# S7CAS-PLEIADES-CARTE-MERE_P06_POWER2.net
KiCad netlist of a schematic drawn in Altium Designer
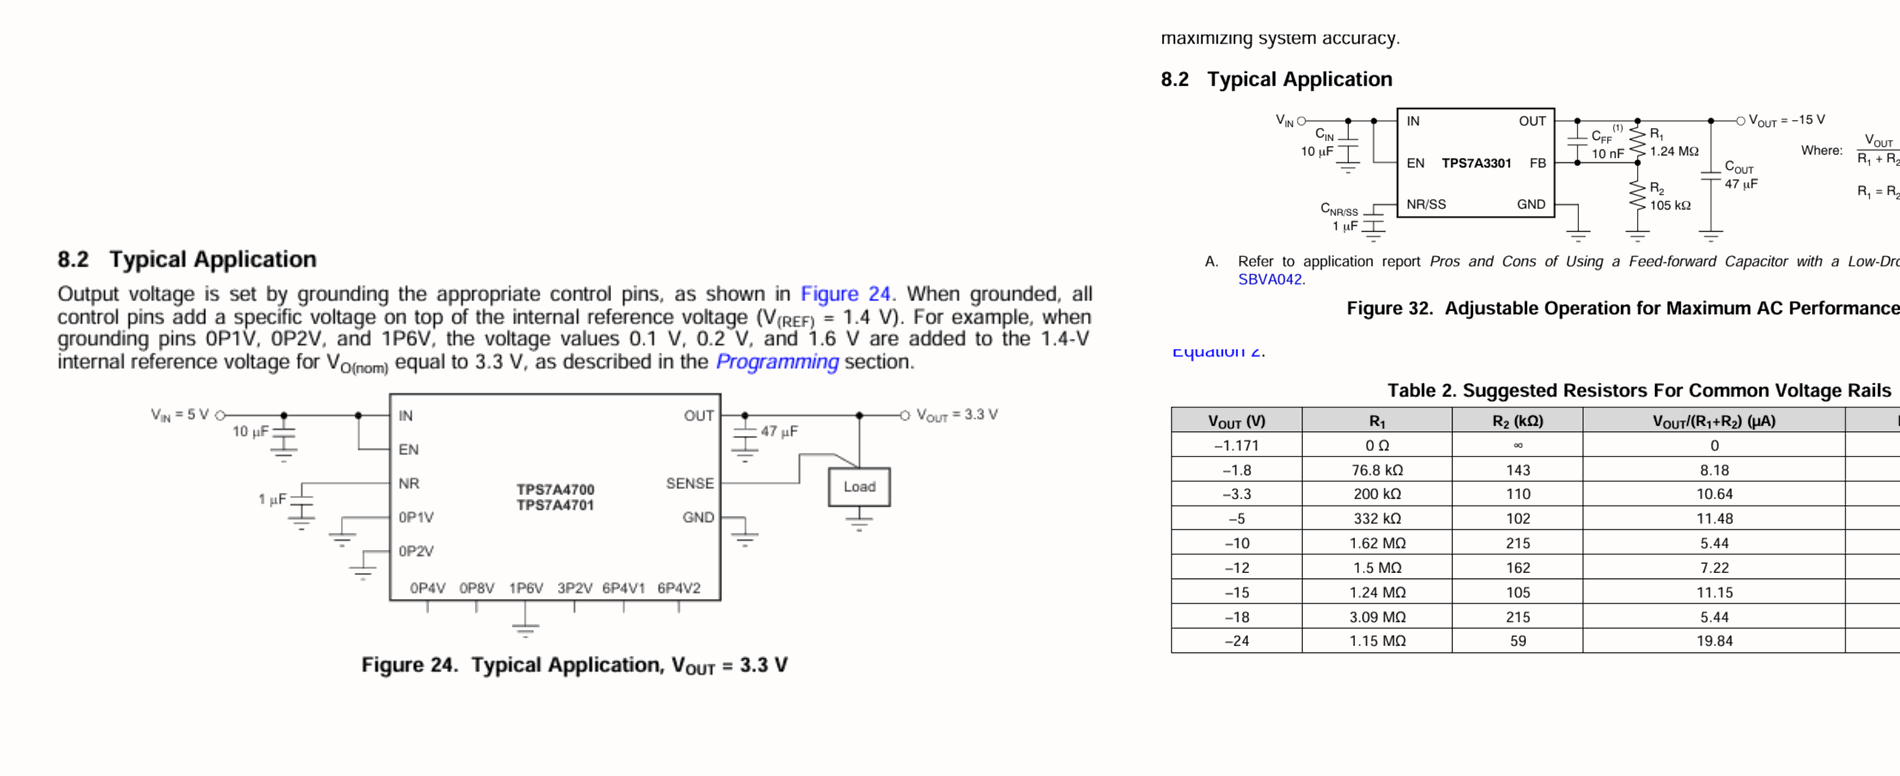
[diagram p0: S7CAS-PLEIADES-CARTE-MERE_P06_POWER2.SCHDOC, top left]
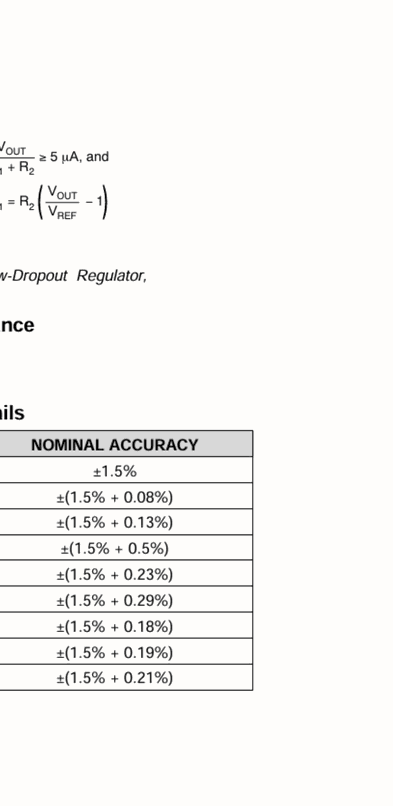
[diagram p1: S7CAS-PLEIADES-CARTE-MERE_P06_POWER2.SCHDOC, top right]
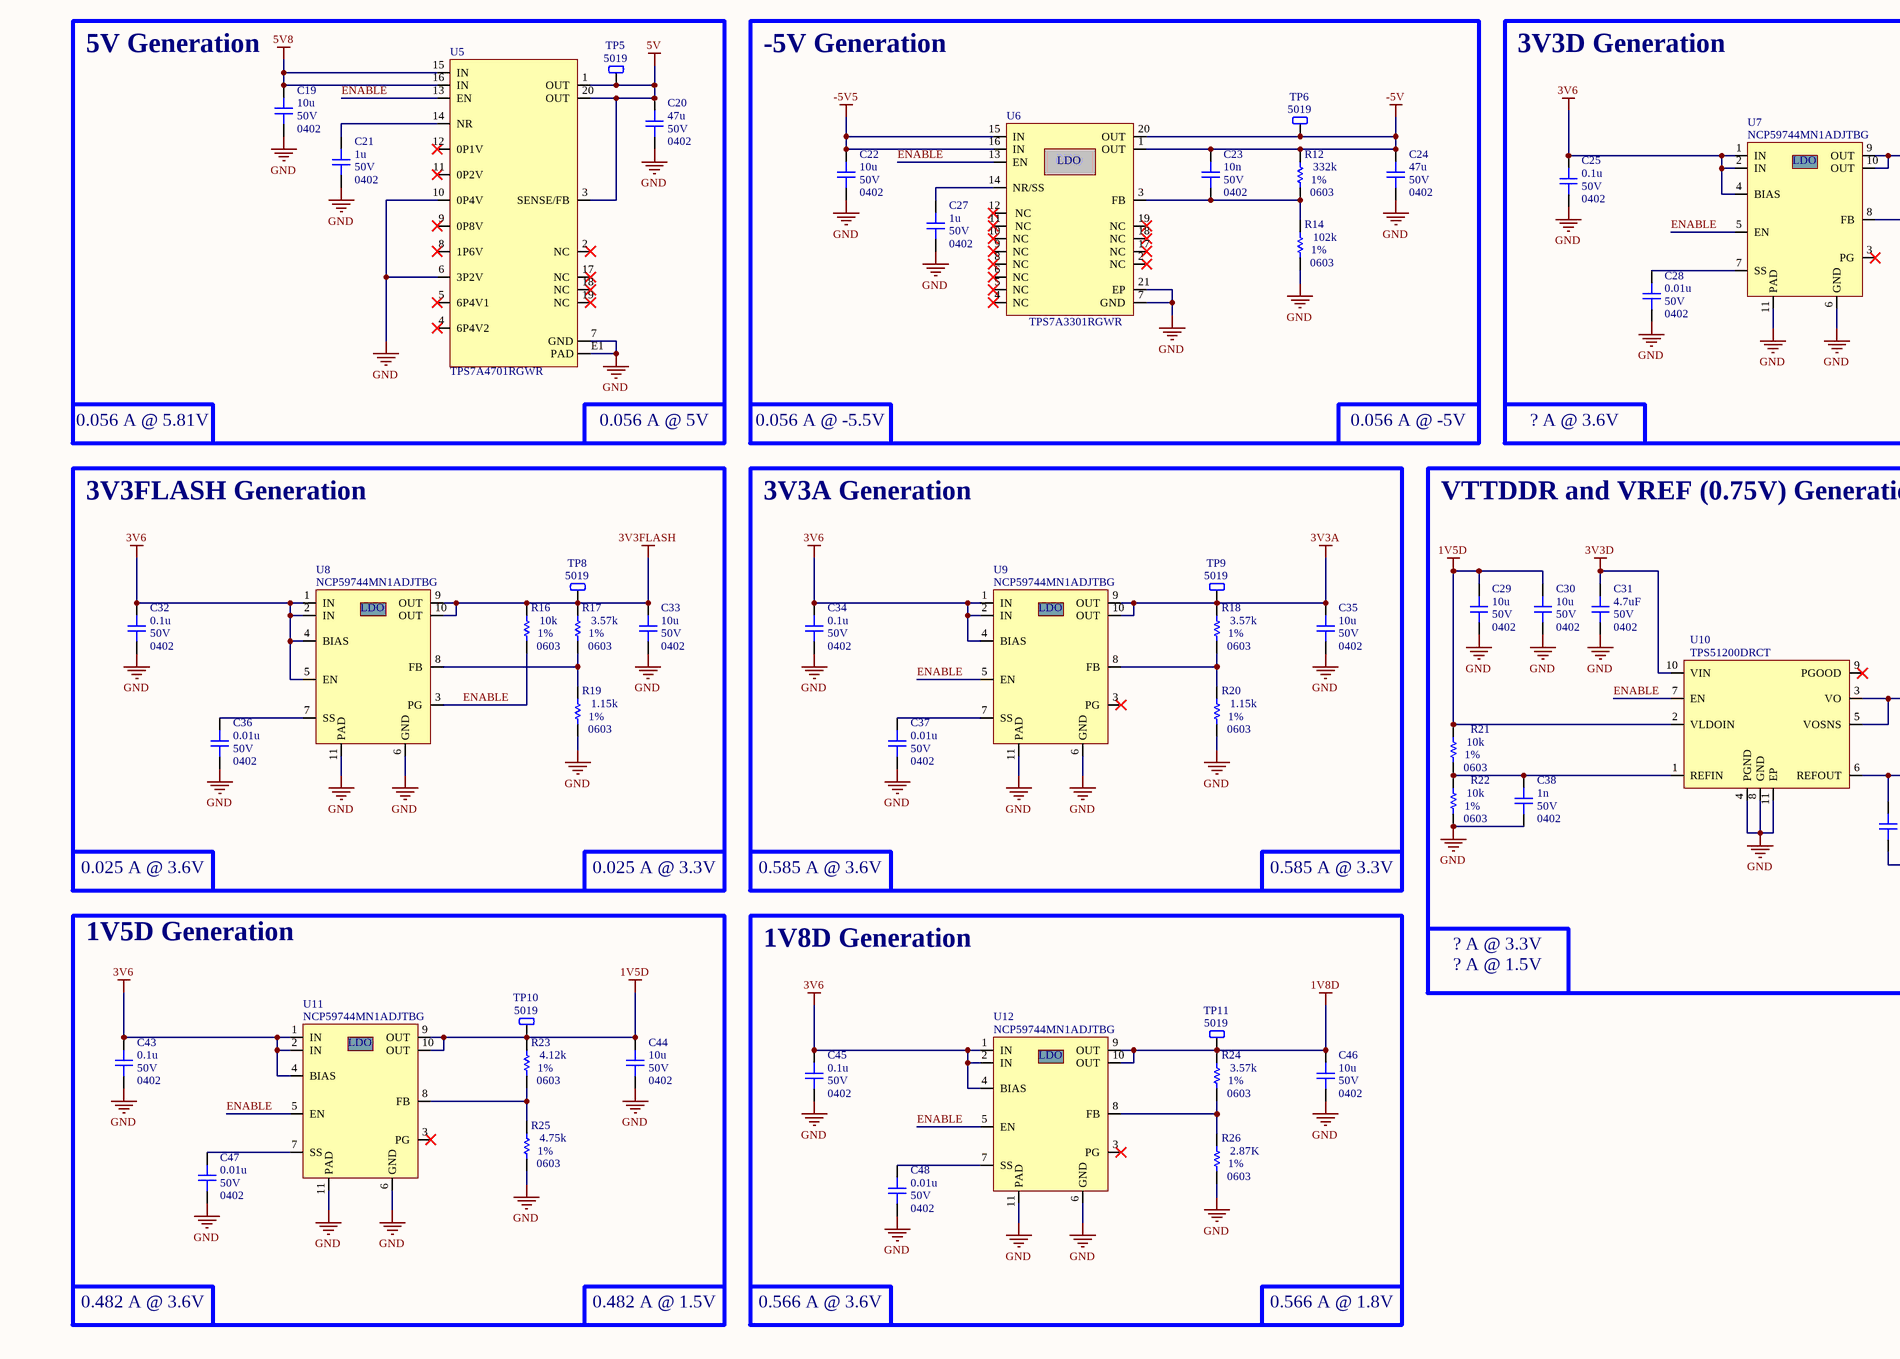
[diagram p2: S7CAS-PLEIADES-CARTE-MERE_P06_POWER2.SCHDOC, bottom left]
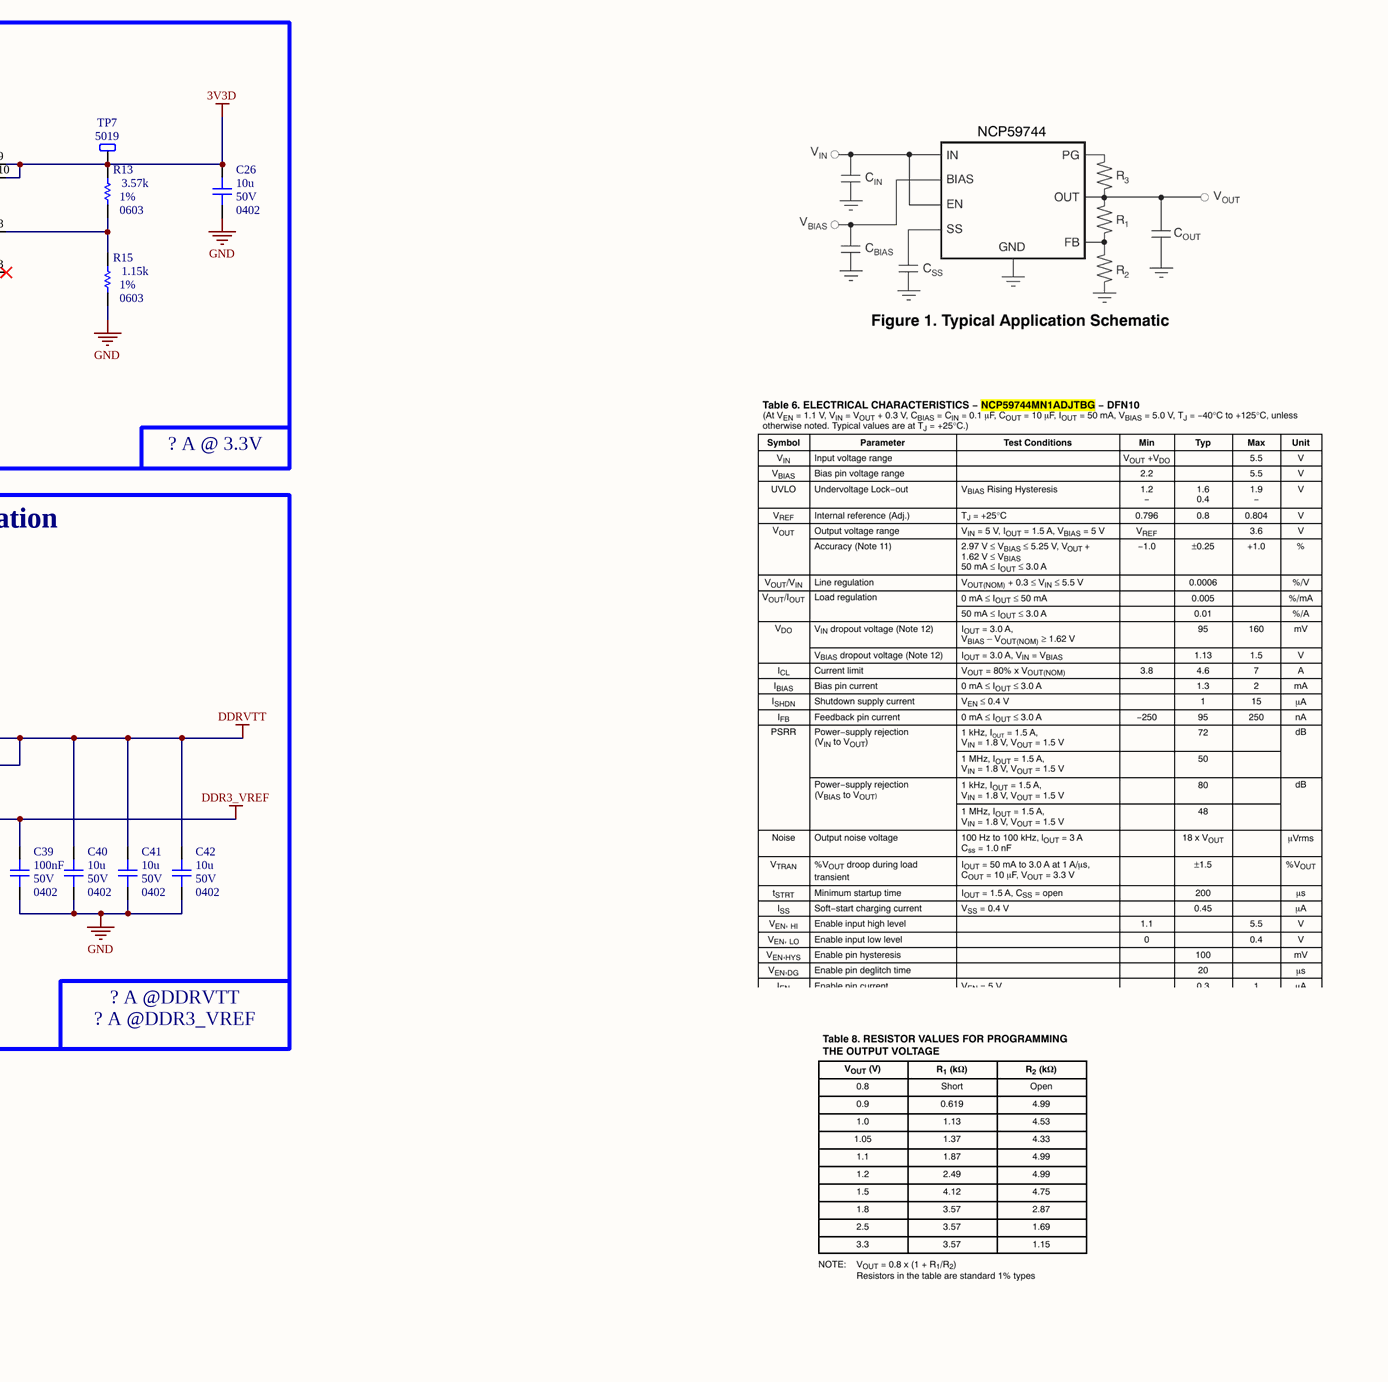
[diagram p3: S7CAS-PLEIADES-CARTE-MERE_P06_POWER2.SCHDOC, bottom right]

(export (version "E")
  (design (tool "Eeschema 10.0.6"))
  (components
    (comp (ref "C19")
      (value "10u")
      (footprint "CAP_0402")
      (description "CAP - 0402")
      (fields
        (field (name "VOLTAGE") "50V")
        (field (name "PACKAGE") "0402")
        (field (name "CREATEDBY") "Jonathan Bouchard")
      )
      (libsource (lib "s7cas_lib2023") (part "CAP - 0402"))
    )
    (comp (ref "C20")
      (value "47u")
      (footprint "CAP_0402")
      (description "CAP - 0402")
      (fields
        (field (name "VOLTAGE") "50V")
        (field (name "PACKAGE") "0402")
        (field (name "CREATEDBY") "Jonathan Bouchard")
      )
      (libsource (lib "s7cas_lib2023") (part "CAP - 0402"))
    )
    (comp (ref "C21")
      (value "1u")
      (footprint "CAP_0402")
      (description "CAP - 0402")
      (fields
        (field (name "VOLTAGE") "50V")
        (field (name "PACKAGE") "0402")
        (field (name "CREATEDBY") "Jonathan Bouchard")
      )
      (libsource (lib "s7cas_lib2023") (part "CAP - 0402"))
    )
    (comp (ref "C22")
      (value "10u")
      (footprint "CAP_0402")
      (description "CAP - 0402")
      (fields
        (field (name "VOLTAGE") "50V")
        (field (name "PACKAGE") "0402")
        (field (name "CREATEDBY") "Jonathan Bouchard")
      )
      (libsource (lib "s7cas_lib2023") (part "CAP - 0402"))
    )
    (comp (ref "C23")
      (value "10n")
      (footprint "CAP_0402")
      (description "CAP - 0402")
      (fields
        (field (name "VOLTAGE") "50V")
        (field (name "PACKAGE") "0402")
        (field (name "CREATEDBY") "Jonathan Bouchard")
      )
      (libsource (lib "s7cas_lib2023") (part "CAP - 0402"))
    )
    (comp (ref "C24")
      (value "47u")
      (footprint "CAP_0402")
      (description "CAP - 0402")
      (fields
        (field (name "VOLTAGE") "50V")
        (field (name "PACKAGE") "0402")
        (field (name "CREATEDBY") "Jonathan Bouchard")
      )
      (libsource (lib "s7cas_lib2023") (part "CAP - 0402"))
    )
    (comp (ref "C25")
      (value "0.1u")
      (footprint "CAP_0402")
      (description "CAP - 0402")
      (fields
        (field (name "VOLTAGE") "50V")
        (field (name "PACKAGE") "0402")
        (field (name "CREATEDBY") "Jonathan Bouchard")
      )
      (libsource (lib "s7cas_lib2023") (part "CAP - 0402"))
    )
    (comp (ref "C26")
      (value "10u")
      (footprint "CAP_0402")
      (description "CAP - 0402")
      (fields
        (field (name "VOLTAGE") "50V")
        (field (name "PACKAGE") "0402")
        (field (name "CREATEDBY") "Jonathan Bouchard")
      )
      (libsource (lib "s7cas_lib2023") (part "CAP - 0402"))
    )
    (comp (ref "C27")
      (value "1u")
      (footprint "CAP_0402")
      (description "CAP - 0402")
      (fields
        (field (name "VOLTAGE") "50V")
        (field (name "PACKAGE") "0402")
        (field (name "CREATEDBY") "Jonathan Bouchard")
      )
      (libsource (lib "s7cas_lib2023") (part "CAP - 0402"))
    )
    (comp (ref "C28")
      (value "0.01u")
      (footprint "CAP_0402")
      (description "CAP - 0402")
      (fields
        (field (name "VOLTAGE") "50V")
        (field (name "PACKAGE") "0402")
        (field (name "CREATEDBY") "Jonathan Bouchard")
      )
      (libsource (lib "s7cas_lib2023") (part "CAP - 0402"))
    )
    (comp (ref "C29")
      (value "10u")
      (footprint "CAP_0402")
      (description "CAP - 0402")
      (fields
        (field (name "VOLTAGE") "50V")
        (field (name "PACKAGE") "0402")
        (field (name "CREATEDBY") "Jonathan Bouchard")
      )
      (libsource (lib "s7cas_lib2023") (part "CAP - 0402"))
    )
    (comp (ref "C30")
      (value "10u")
      (footprint "CAP_0402")
      (description "CAP - 0402")
      (fields
        (field (name "VOLTAGE") "50V")
        (field (name "PACKAGE") "0402")
        (field (name "CREATEDBY") "Jonathan Bouchard")
      )
      (libsource (lib "s7cas_lib2023") (part "CAP - 0402"))
    )
    (comp (ref "C31")
      (value "4.7uF")
      (footprint "CAP_0402")
      (description "CAP - 0402")
      (fields
        (field (name "VOLTAGE") "50V")
        (field (name "PACKAGE") "0402")
        (field (name "CREATEDBY") "Jonathan Bouchard")
      )
      (libsource (lib "s7cas_lib2023") (part "CAP - 0402"))
    )
    (comp (ref "C32")
      (value "0.1u")
      (footprint "CAP_0402")
      (description "CAP - 0402")
      (fields
        (field (name "VOLTAGE") "50V")
        (field (name "PACKAGE") "0402")
        (field (name "CREATEDBY") "Jonathan Bouchard")
      )
      (libsource (lib "s7cas_lib2023") (part "CAP - 0402"))
    )
    (comp (ref "C33")
      (value "10u")
      (footprint "CAP_0402")
      (description "CAP - 0402")
      (fields
        (field (name "VOLTAGE") "50V")
        (field (name "PACKAGE") "0402")
        (field (name "CREATEDBY") "Jonathan Bouchard")
      )
      (libsource (lib "s7cas_lib2023") (part "CAP - 0402"))
    )
    (comp (ref "C34")
      (value "0.1u")
      (footprint "CAP_0402")
      (description "CAP - 0402")
      (fields
        (field (name "VOLTAGE") "50V")
        (field (name "PACKAGE") "0402")
        (field (name "CREATEDBY") "Jonathan Bouchard")
      )
      (libsource (lib "s7cas_lib2023") (part "CAP - 0402"))
    )
    (comp (ref "C35")
      (value "10u")
      (footprint "CAP_0402")
      (description "CAP - 0402")
      (fields
        (field (name "VOLTAGE") "50V")
        (field (name "PACKAGE") "0402")
        (field (name "CREATEDBY") "Jonathan Bouchard")
      )
      (libsource (lib "s7cas_lib2023") (part "CAP - 0402"))
    )
    (comp (ref "C36")
      (value "0.01u")
      (footprint "CAP_0402")
      (description "CAP - 0402")
      (fields
        (field (name "VOLTAGE") "50V")
        (field (name "PACKAGE") "0402")
        (field (name "CREATEDBY") "Jonathan Bouchard")
      )
      (libsource (lib "s7cas_lib2023") (part "CAP - 0402"))
    )
    (comp (ref "C37")
      (value "0.01u")
      (footprint "CAP_0402")
      (description "CAP - 0402")
      (fields
        (field (name "VOLTAGE") "50V")
        (field (name "PACKAGE") "0402")
        (field (name "CREATEDBY") "Jonathan Bouchard")
      )
      (libsource (lib "s7cas_lib2023") (part "CAP - 0402"))
    )
    (comp (ref "C38")
      (value "1n")
      (footprint "CAP_0402")
      (description "CAP - 0402")
      (fields
        (field (name "VOLTAGE") "50V")
        (field (name "PACKAGE") "0402")
        (field (name "CREATEDBY") "Jonathan Bouchard")
      )
      (libsource (lib "s7cas_lib2023") (part "CAP - 0402"))
    )
    (comp (ref "C39")
      (value "100nF")
      (footprint "CAP_0402")
      (description "CAP - 0402")
      (fields
        (field (name "VOLTAGE") "50V")
        (field (name "PACKAGE") "0402")
        (field (name "CREATEDBY") "Jonathan Bouchard")
      )
      (libsource (lib "s7cas_lib2023") (part "CAP - 0402"))
    )
    (comp (ref "C40")
      (value "10u")
      (footprint "CAP_0402")
      (description "CAP - 0402")
      (fields
        (field (name "VOLTAGE") "50V")
        (field (name "PACKAGE") "0402")
        (field (name "CREATEDBY") "Jonathan Bouchard")
      )
      (libsource (lib "s7cas_lib2023") (part "CAP - 0402"))
    )
    (comp (ref "C41")
      (value "10u")
      (footprint "CAP_0402")
      (description "CAP - 0402")
      (fields
        (field (name "VOLTAGE") "50V")
        (field (name "PACKAGE") "0402")
        (field (name "CREATEDBY") "Jonathan Bouchard")
      )
      (libsource (lib "s7cas_lib2023") (part "CAP - 0402"))
    )
    (comp (ref "C42")
      (value "10u")
      (footprint "CAP_0402")
      (description "CAP - 0402")
      (fields
        (field (name "VOLTAGE") "50V")
        (field (name "PACKAGE") "0402")
        (field (name "CREATEDBY") "Jonathan Bouchard")
      )
      (libsource (lib "s7cas_lib2023") (part "CAP - 0402"))
    )
    (comp (ref "C43")
      (value "0.1u")
      (footprint "CAP_0402")
      (description "CAP - 0402")
      (fields
        (field (name "VOLTAGE") "50V")
        (field (name "PACKAGE") "0402")
        (field (name "CREATEDBY") "Jonathan Bouchard")
      )
      (libsource (lib "s7cas_lib2023") (part "CAP - 0402"))
    )
    (comp (ref "C44")
      (value "10u")
      (footprint "CAP_0402")
      (description "CAP - 0402")
      (fields
        (field (name "VOLTAGE") "50V")
        (field (name "PACKAGE") "0402")
        (field (name "CREATEDBY") "Jonathan Bouchard")
      )
      (libsource (lib "s7cas_lib2023") (part "CAP - 0402"))
    )
    (comp (ref "C45")
      (value "0.1u")
      (footprint "CAP_0402")
      (description "CAP - 0402")
      (fields
        (field (name "VOLTAGE") "50V")
        (field (name "PACKAGE") "0402")
        (field (name "CREATEDBY") "Jonathan Bouchard")
      )
      (libsource (lib "s7cas_lib2023") (part "CAP - 0402"))
    )
    (comp (ref "C46")
      (value "10u")
      (footprint "CAP_0402")
      (description "CAP - 0402")
      (fields
        (field (name "VOLTAGE") "50V")
        (field (name "PACKAGE") "0402")
        (field (name "CREATEDBY") "Jonathan Bouchard")
      )
      (libsource (lib "s7cas_lib2023") (part "CAP - 0402"))
    )
    (comp (ref "C47")
      (value "0.01u")
      (footprint "CAP_0402")
      (description "CAP - 0402")
      (fields
        (field (name "VOLTAGE") "50V")
        (field (name "PACKAGE") "0402")
        (field (name "CREATEDBY") "Jonathan Bouchard")
      )
      (libsource (lib "s7cas_lib2023") (part "CAP - 0402"))
    )
    (comp (ref "C48")
      (value "0.01u")
      (footprint "CAP_0402")
      (description "CAP - 0402")
      (fields
        (field (name "VOLTAGE") "50V")
        (field (name "PACKAGE") "0402")
        (field (name "CREATEDBY") "Jonathan Bouchard")
      )
      (libsource (lib "s7cas_lib2023") (part "CAP - 0402"))
    )
    (comp (ref "R12")
      (value "332k")
      (footprint "RES_0603")
      (description "RES - 0603")
      (fields
        (field (name "PACKAGE") "0603")
        (field (name "PRECISION") "1%")
        (field (name "CREATEDBY") "Jonathan Bouchard")
      )
      (libsource (lib "s7cas_lib2023") (part "RES - 0603"))
    )
    (comp (ref "R13")
      (value "3.57k")
      (footprint "RES_0603")
      (description "RES - 0603")
      (fields
        (field (name "PACKAGE") "0603")
        (field (name "PRECISION") "1%")
        (field (name "CREATEDBY") "Jonathan Bouchard")
      )
      (libsource (lib "s7cas_lib2023") (part "RES - 0603"))
    )
    (comp (ref "R14")
      (value "102k")
      (footprint "RES_0603")
      (description "RES - 0603")
      (fields
        (field (name "PACKAGE") "0603")
        (field (name "PRECISION") "1%")
        (field (name "CREATEDBY") "Jonathan Bouchard")
      )
      (libsource (lib "s7cas_lib2023") (part "RES - 0603"))
    )
    (comp (ref "R15")
      (value "1.15k")
      (footprint "RES_0603")
      (description "RES - 0603")
      (fields
        (field (name "PACKAGE") "0603")
        (field (name "PRECISION") "1%")
        (field (name "CREATEDBY") "Jonathan Bouchard")
      )
      (libsource (lib "s7cas_lib2023") (part "RES - 0603"))
    )
    (comp (ref "R16")
      (value "10k")
      (footprint "RES_0603")
      (description "RES - 0603")
      (fields
        (field (name "PACKAGE") "0603")
        (field (name "PRECISION") "1%")
        (field (name "CREATEDBY") "Jonathan Bouchard")
      )
      (libsource (lib "s7cas_lib2023") (part "RES - 0603"))
    )
    (comp (ref "R17")
      (value "3.57k")
      (footprint "RES_0603")
      (description "RES - 0603")
      (fields
        (field (name "PACKAGE") "0603")
        (field (name "PRECISION") "1%")
        (field (name "CREATEDBY") "Jonathan Bouchard")
      )
      (libsource (lib "s7cas_lib2023") (part "RES - 0603"))
    )
    (comp (ref "R18")
      (value "3.57k")
      (footprint "RES_0603")
      (description "RES - 0603")
      (fields
        (field (name "PACKAGE") "0603")
        (field (name "PRECISION") "1%")
        (field (name "CREATEDBY") "Jonathan Bouchard")
      )
      (libsource (lib "s7cas_lib2023") (part "RES - 0603"))
    )
    (comp (ref "R19")
      (value "1.15k")
      (footprint "RES_0603")
      (description "RES - 0603")
      (fields
        (field (name "PACKAGE") "0603")
        (field (name "PRECISION") "1%")
        (field (name "CREATEDBY") "Jonathan Bouchard")
      )
      (libsource (lib "s7cas_lib2023") (part "RES - 0603"))
    )
    (comp (ref "R20")
      (value "1.15k")
      (footprint "RES_0603")
      (description "RES - 0603")
      (fields
        (field (name "PACKAGE") "0603")
        (field (name "PRECISION") "1%")
        (field (name "CREATEDBY") "Jonathan Bouchard")
      )
      (libsource (lib "s7cas_lib2023") (part "RES - 0603"))
    )
    (comp (ref "R21")
      (value "10k")
      (footprint "RES_0603")
      (description "RES - 0603")
      (fields
        (field (name "PACKAGE") "0603")
        (field (name "PRECISION") "1%")
        (field (name "CREATEDBY") "Jonathan Bouchard")
      )
      (libsource (lib "s7cas_lib2023") (part "RES - 0603"))
    )
    (comp (ref "R22")
      (value "10k")
      (footprint "RES_0603")
      (description "RES - 0603")
      (fields
        (field (name "PACKAGE") "0603")
        (field (name "PRECISION") "1%")
        (field (name "CREATEDBY") "Jonathan Bouchard")
      )
      (libsource (lib "s7cas_lib2023") (part "RES - 0603"))
    )
    (comp (ref "R23")
      (value "4.12k")
      (footprint "RES_0603")
      (description "RES - 0603")
      (fields
        (field (name "PACKAGE") "0603")
        (field (name "PRECISION") "1%")
        (field (name "CREATEDBY") "Jonathan Bouchard")
      )
      (libsource (lib "s7cas_lib2023") (part "RES - 0603"))
    )
    (comp (ref "R24")
      (value "3.57k")
      (footprint "RES_0603")
      (description "RES - 0603")
      (fields
        (field (name "PACKAGE") "0603")
        (field (name "PRECISION") "1%")
        (field (name "CREATEDBY") "Jonathan Bouchard")
      )
      (libsource (lib "s7cas_lib2023") (part "RES - 0603"))
    )
    (comp (ref "R25")
      (value "4.75k")
      (footprint "RES_0603")
      (description "RES - 0603")
      (fields
        (field (name "PACKAGE") "0603")
        (field (name "PRECISION") "1%")
        (field (name "CREATEDBY") "Jonathan Bouchard")
      )
      (libsource (lib "s7cas_lib2023") (part "RES - 0603"))
    )
    (comp (ref "R26")
      (value "2.87K")
      (footprint "RES_0603")
      (description "RES - 0603")
      (fields
        (field (name "PACKAGE") "0603")
        (field (name "PRECISION") "1%")
        (field (name "CREATEDBY") "Jonathan Bouchard")
      )
      (libsource (lib "s7cas_lib2023") (part "RES - 0603"))
    )
    (comp (ref "TP5")
      (value "5019")
      (footprint "TPO_SMD_5019")
      (description "TPO - PC TEST POINT MINI - SMD")
      (fields
        (field (name "CREATEDBY/DATE") "Olivier Bernard / 5/12/2017")
        (field (name "VERIFIEDBY") "Caroline Paulin / 5 juillet 2018")
      )
      (libsource (lib "s7cas_lib2023") (part "TPO_SMD_5019"))
    )
    (comp (ref "TP6")
      (value "5019")
      (footprint "TPO_SMD_5019")
      (description "TPO - PC TEST POINT MINI - SMD")
      (fields
        (field (name "CREATEDBY/DATE") "Olivier Bernard / 5/12/2017")
        (field (name "VERIFIEDBY") "Caroline Paulin / 5 juillet 2018")
      )
      (libsource (lib "s7cas_lib2023") (part "TPO_SMD_5019"))
    )
    (comp (ref "TP7")
      (value "5019")
      (footprint "TPO_SMD_5019")
      (description "TPO - PC TEST POINT MINI - SMD")
      (fields
        (field (name "CREATEDBY/DATE") "Olivier Bernard / 5/12/2017")
        (field (name "VERIFIEDBY") "Caroline Paulin / 5 juillet 2018")
      )
      (libsource (lib "s7cas_lib2023") (part "TPO_SMD_5019"))
    )
    (comp (ref "TP8")
      (value "5019")
      (footprint "TPO_SMD_5019")
      (description "TPO - PC TEST POINT MINI - SMD")
      (fields
        (field (name "CREATEDBY/DATE") "Olivier Bernard / 5/12/2017")
        (field (name "VERIFIEDBY") "Caroline Paulin / 5 juillet 2018")
      )
      (libsource (lib "s7cas_lib2023") (part "TPO_SMD_5019"))
    )
    (comp (ref "TP9")
      (value "5019")
      (footprint "TPO_SMD_5019")
      (description "TPO - PC TEST POINT MINI - SMD")
      (fields
        (field (name "CREATEDBY/DATE") "Olivier Bernard / 5/12/2017")
        (field (name "VERIFIEDBY") "Caroline Paulin / 5 juillet 2018")
      )
      (libsource (lib "s7cas_lib2023") (part "TPO_SMD_5019"))
    )
    (comp (ref "TP10")
      (value "5019")
      (footprint "TPO_SMD_5019")
      (description "TPO - PC TEST POINT MINI - SMD")
      (fields
        (field (name "CREATEDBY/DATE") "Olivier Bernard / 5/12/2017")
        (field (name "VERIFIEDBY") "Caroline Paulin / 5 juillet 2018")
      )
      (libsource (lib "s7cas_lib2023") (part "TPO_SMD_5019"))
    )
    (comp (ref "TP11")
      (value "5019")
      (footprint "TPO_SMD_5019")
      (description "TPO - PC TEST POINT MINI - SMD")
      (fields
        (field (name "CREATEDBY/DATE") "Olivier Bernard / 5/12/2017")
        (field (name "VERIFIEDBY") "Caroline Paulin / 5 juillet 2018")
      )
      (libsource (lib "s7cas_lib2023") (part "TPO_SMD_5019"))
    )
    (comp (ref "U5")
      (value "TPS7A4701RGWR")
      (footprint "REG_TPS7A4701RGWR")
      (description "REG - LINEAR POS ADJ 1A - 20VQFN")
      (fields
        (field (name "CREATEDBY/DATE") "L-P Gauthier / 2018-05-29")
        (field (name "VERIFIEDBY") "Caroline Paulin - 28 sept 2018")
      )
      (libsource (lib "s7cas_lib2023") (part "REG_LDO_TPS7A4701RGWR"))
    )
    (comp (ref "U6")
      (value "TPS7A3301RGWR")
      (footprint "REG_LDO_TPS7A3301RGWR")
      (description "REG - LDO Negative Adjustable 1 Output -1.18V-33V 1A -  20-VQFN (5x5)")
      (fields
        (field (name "CREATEDBY/DATE") "Keven Deslandes - 2018/10/11")
        (field (name "VERIFIEDBY") "Caroline Paulin - 11/12/2018")
      )
      (libsource (lib "s7cas_lib2023") (part "REG_LDO_TPS7A3301RGWR"))
    )
    (comp (ref "U7")
      (value "NCP59744MN1ADJTBG")
      (footprint "REG_LDO_NCP59744MN1ADJTBG")
      (description "REG - LINEAR POS ADJ 3A BIAS - 10-VFDFN")
      (fields
        (field (name "CREATEDBY/DATE") "Raphael Bouchard / 2019-06-07")
        (field (name "VERIFIEDBY") "C.Paulin - 13/06/2019")
      )
      (libsource (lib "s7cas_lib2023") (part "REG_LDO_NCP59744MN1ADJTBG"))
    )
    (comp (ref "U8")
      (value "NCP59744MN1ADJTBG")
      (footprint "REG_LDO_NCP59744MN1ADJTBG")
      (description "REG - LINEAR POS ADJ 3A BIAS - 10-VFDFN")
      (fields
        (field (name "CREATEDBY/DATE") "Raphael Bouchard / 2019-06-07")
        (field (name "VERIFIEDBY") "C.Paulin - 13/06/2019")
      )
      (libsource (lib "s7cas_lib2023") (part "REG_LDO_NCP59744MN1ADJTBG"))
    )
    (comp (ref "U9")
      (value "NCP59744MN1ADJTBG")
      (footprint "REG_LDO_NCP59744MN1ADJTBG")
      (description "REG - LINEAR POS ADJ 3A BIAS - 10-VFDFN")
      (fields
        (field (name "CREATEDBY/DATE") "Raphael Bouchard / 2019-06-07")
        (field (name "VERIFIEDBY") "C.Paulin - 13/06/2019")
      )
      (libsource (lib "s7cas_lib2023") (part "REG_LDO_NCP59744MN1ADJTBG"))
    )
    (comp (ref "U10")
      (value "TPS51200DRCT")
      (footprint "REG_PMIC_TPS51200DRCT")
      (description "REG - DDR TERMINATION/REF REG - 10-VFDFN")
      (fields
        (field (name "CREATEDBY/DATE") "Joel Lemay 2019-03-19")
        (field (name "VERIFIEDBY") "Nicolas V. (2019-05-31)")
      )
      (libsource (lib "s7cas_lib2023") (part "REG_PMIC_TPS51200DRCT"))
    )
    (comp (ref "U11")
      (value "NCP59744MN1ADJTBG")
      (footprint "REG_LDO_NCP59744MN1ADJTBG")
      (description "REG - LINEAR POS ADJ 3A BIAS - 10-VFDFN")
      (fields
        (field (name "CREATEDBY/DATE") "Raphael Bouchard / 2019-06-07")
        (field (name "VERIFIEDBY") "C.Paulin - 13/06/2019")
      )
      (libsource (lib "s7cas_lib2023") (part "REG_LDO_NCP59744MN1ADJTBG"))
    )
    (comp (ref "U12")
      (value "NCP59744MN1ADJTBG")
      (footprint "REG_LDO_NCP59744MN1ADJTBG")
      (description "REG - LINEAR POS ADJ 3A BIAS - 10-VFDFN")
      (fields
        (field (name "CREATEDBY/DATE") "Raphael Bouchard / 2019-06-07")
        (field (name "VERIFIEDBY") "C.Paulin - 13/06/2019")
      )
      (libsource (lib "s7cas_lib2023") (part "REG_LDO_NCP59744MN1ADJTBG"))
    )
  )
  (nets
    (net (code "1") (name "-5V") (class "Default")
      (node (ref "C23") (pin "2") (pinfunction "2_2") (pintype "passive"))
      (node (ref "C24") (pin "2") (pinfunction "2_2") (pintype "passive"))
      (node (ref "R12") (pin "2") (pinfunction "2_2") (pintype "passive"))
      (node (ref "TP6") (pin "1") (pinfunction "1_1") (pintype "passive"))
      (node (ref "U6") (pin "1") (pinfunction "OUT_1") (pintype "passive"))
      (node (ref "U6") (pin "20") (pinfunction "OUT_20") (pintype "passive"))
    )
    (net (code "2") (name "-5V5") (class "Default")
      (node (ref "C22") (pin "2") (pinfunction "2_2") (pintype "passive"))
      (node (ref "U6") (pin "15") (pinfunction "IN_15") (pintype "passive"))
      (node (ref "U6") (pin "16") (pinfunction "IN_16") (pintype "passive"))
    )
    (net (code "3") (name "/ENABLE") (class "Default")
      (node (ref "R16") (pin "1") (pinfunction "1_1") (pintype "passive"))
      (node (ref "U10") (pin "7") (pinfunction "EN_7") (pintype "passive"))
      (node (ref "U11") (pin "5") (pinfunction "EN_5") (pintype "passive"))
      (node (ref "U12") (pin "5") (pinfunction "EN_5") (pintype "passive"))
      (node (ref "U5") (pin "13") (pinfunction "EN_13") (pintype "passive"))
      (node (ref "U6") (pin "13") (pinfunction "EN_13") (pintype "passive"))
      (node (ref "U7") (pin "5") (pinfunction "EN_5") (pintype "passive"))
      (node (ref "U8") (pin "3") (pinfunction "PG_3") (pintype "passive"))
      (node (ref "U9") (pin "5") (pinfunction "EN_5") (pintype "passive"))
    )
    (net (code "4") (name "1V5D") (class "Default")
      (node (ref "C29") (pin "2") (pinfunction "2_2") (pintype "passive"))
      (node (ref "C30") (pin "2") (pinfunction "2_2") (pintype "passive"))
      (node (ref "C44") (pin "2") (pinfunction "2_2") (pintype "passive"))
      (node (ref "R21") (pin "2") (pinfunction "2_2") (pintype "passive"))
      (node (ref "R23") (pin "2") (pinfunction "2_2") (pintype "passive"))
      (node (ref "TP10") (pin "1") (pinfunction "1_1") (pintype "passive"))
      (node (ref "U10") (pin "2") (pinfunction "VLDOIN_2") (pintype "passive"))
      (node (ref "U11") (pin "10") (pinfunction "OUT_10") (pintype "passive"))
      (node (ref "U11") (pin "9") (pinfunction "OUT_9") (pintype "passive"))
    )
    (net (code "5") (name "1V8D") (class "Default")
      (node (ref "C46") (pin "2") (pinfunction "2_2") (pintype "passive"))
      (node (ref "R24") (pin "2") (pinfunction "2_2") (pintype "passive"))
      (node (ref "TP11") (pin "1") (pinfunction "1_1") (pintype "passive"))
      (node (ref "U12") (pin "10") (pinfunction "OUT_10") (pintype "passive"))
      (node (ref "U12") (pin "9") (pinfunction "OUT_9") (pintype "passive"))
    )
    (net (code "6") (name "3V3A") (class "Default")
      (node (ref "C35") (pin "2") (pinfunction "2_2") (pintype "passive"))
      (node (ref "R18") (pin "2") (pinfunction "2_2") (pintype "passive"))
      (node (ref "TP9") (pin "1") (pinfunction "1_1") (pintype "passive"))
      (node (ref "U9") (pin "10") (pinfunction "OUT_10") (pintype "passive"))
      (node (ref "U9") (pin "9") (pinfunction "OUT_9") (pintype "passive"))
    )
    (net (code "7") (name "3V3D") (class "Default")
      (node (ref "C26") (pin "2") (pinfunction "2_2") (pintype "passive"))
      (node (ref "C31") (pin "2") (pinfunction "2_2") (pintype "passive"))
      (node (ref "R13") (pin "2") (pinfunction "2_2") (pintype "passive"))
      (node (ref "TP7") (pin "1") (pinfunction "1_1") (pintype "passive"))
      (node (ref "U10") (pin "10") (pinfunction "VIN_10") (pintype "passive"))
      (node (ref "U7") (pin "10") (pinfunction "OUT_10") (pintype "passive"))
      (node (ref "U7") (pin "9") (pinfunction "OUT_9") (pintype "passive"))
    )
    (net (code "8") (name "3V3FLASH") (class "Default")
      (node (ref "C33") (pin "2") (pinfunction "2_2") (pintype "passive"))
      (node (ref "R16") (pin "2") (pinfunction "2_2") (pintype "passive"))
      (node (ref "R17") (pin "2") (pinfunction "2_2") (pintype "passive"))
      (node (ref "TP8") (pin "1") (pinfunction "1_1") (pintype "passive"))
      (node (ref "U8") (pin "10") (pinfunction "OUT_10") (pintype "passive"))
      (node (ref "U8") (pin "9") (pinfunction "OUT_9") (pintype "passive"))
    )
    (net (code "9") (name "3V6") (class "Default")
      (node (ref "C25") (pin "2") (pinfunction "2_2") (pintype "passive"))
      (node (ref "C32") (pin "2") (pinfunction "2_2") (pintype "passive"))
      (node (ref "C34") (pin "2") (pinfunction "2_2") (pintype "passive"))
      (node (ref "C43") (pin "2") (pinfunction "2_2") (pintype "passive"))
      (node (ref "C45") (pin "2") (pinfunction "2_2") (pintype "passive"))
      (node (ref "U11") (pin "1") (pinfunction "IN_1") (pintype "passive"))
      (node (ref "U11") (pin "2") (pinfunction "IN_2") (pintype "passive"))
      (node (ref "U11") (pin "4") (pinfunction "BIAS_4") (pintype "passive"))
      (node (ref "U12") (pin "1") (pinfunction "IN_1") (pintype "passive"))
      (node (ref "U12") (pin "2") (pinfunction "IN_2") (pintype "passive"))
      (node (ref "U12") (pin "4") (pinfunction "BIAS_4") (pintype "passive"))
      (node (ref "U7") (pin "1") (pinfunction "IN_1") (pintype "passive"))
      (node (ref "U7") (pin "2") (pinfunction "IN_2") (pintype "passive"))
      (node (ref "U7") (pin "4") (pinfunction "BIAS_4") (pintype "passive"))
      (node (ref "U8") (pin "1") (pinfunction "IN_1") (pintype "passive"))
      (node (ref "U8") (pin "2") (pinfunction "IN_2") (pintype "passive"))
      (node (ref "U8") (pin "4") (pinfunction "BIAS_4") (pintype "passive"))
      (node (ref "U8") (pin "5") (pinfunction "EN_5") (pintype "passive"))
      (node (ref "U9") (pin "1") (pinfunction "IN_1") (pintype "passive"))
      (node (ref "U9") (pin "2") (pinfunction "IN_2") (pintype "passive"))
      (node (ref "U9") (pin "4") (pinfunction "BIAS_4") (pintype "passive"))
    )
    (net (code "10") (name "5V") (class "Default")
      (node (ref "C20") (pin "2") (pinfunction "2_2") (pintype "passive"))
      (node (ref "TP5") (pin "1") (pinfunction "1_1") (pintype "passive"))
      (node (ref "U5") (pin "1") (pinfunction "OUT_1") (pintype "passive"))
      (node (ref "U5") (pin "20") (pinfunction "OUT_20") (pintype "passive"))
      (node (ref "U5") (pin "3") (pinfunction "SENSE/FB_3") (pintype "passive"))
    )
    (net (code "11") (name "5V8") (class "Default")
      (node (ref "C19") (pin "2") (pinfunction "2_2") (pintype "passive"))
      (node (ref "U5") (pin "15") (pinfunction "IN_15") (pintype "passive"))
      (node (ref "U5") (pin "16") (pinfunction "IN_16") (pintype "passive"))
    )
    (net (code "12") (name "DDR3_VREF") (class "Default")
      (node (ref "C39") (pin "2") (pinfunction "2_2") (pintype "passive"))
      (node (ref "U10") (pin "6") (pinfunction "REFOUT_6") (pintype "passive"))
    )
    (net (code "13") (name "DDRVTT") (class "Default")
      (node (ref "C40") (pin "2") (pinfunction "2_2") (pintype "passive"))
      (node (ref "C41") (pin "2") (pinfunction "2_2") (pintype "passive"))
      (node (ref "C42") (pin "2") (pinfunction "2_2") (pintype "passive"))
      (node (ref "U10") (pin "3") (pinfunction "VO_3") (pintype "passive"))
      (node (ref "U10") (pin "5") (pinfunction "VOSNS_5") (pintype "passive"))
    )
    (net (code "14") (name "GND") (class "Default")
      (node (ref "C19") (pin "1") (pinfunction "1_1") (pintype "passive"))
      (node (ref "C20") (pin "1") (pinfunction "1_1") (pintype "passive"))
      (node (ref "C21") (pin "1") (pinfunction "1_1") (pintype "passive"))
      (node (ref "C22") (pin "1") (pinfunction "1_1") (pintype "passive"))
      (node (ref "C24") (pin "1") (pinfunction "1_1") (pintype "passive"))
      (node (ref "C25") (pin "1") (pinfunction "1_1") (pintype "passive"))
      (node (ref "C26") (pin "1") (pinfunction "1_1") (pintype "passive"))
      (node (ref "C27") (pin "1") (pinfunction "1_1") (pintype "passive"))
      (node (ref "C28") (pin "1") (pinfunction "1_1") (pintype "passive"))
      (node (ref "C29") (pin "1") (pinfunction "1_1") (pintype "passive"))
      (node (ref "C30") (pin "1") (pinfunction "1_1") (pintype "passive"))
      (node (ref "C31") (pin "1") (pinfunction "1_1") (pintype "passive"))
      (node (ref "C32") (pin "1") (pinfunction "1_1") (pintype "passive"))
      (node (ref "C33") (pin "1") (pinfunction "1_1") (pintype "passive"))
      (node (ref "C34") (pin "1") (pinfunction "1_1") (pintype "passive"))
      (node (ref "C35") (pin "1") (pinfunction "1_1") (pintype "passive"))
      (node (ref "C36") (pin "1") (pinfunction "1_1") (pintype "passive"))
      (node (ref "C37") (pin "1") (pinfunction "1_1") (pintype "passive"))
      (node (ref "C38") (pin "1") (pinfunction "1_1") (pintype "passive"))
      (node (ref "C39") (pin "1") (pinfunction "1_1") (pintype "passive"))
      (node (ref "C40") (pin "1") (pinfunction "1_1") (pintype "passive"))
      (node (ref "C41") (pin "1") (pinfunction "1_1") (pintype "passive"))
      (node (ref "C42") (pin "1") (pinfunction "1_1") (pintype "passive"))
      (node (ref "C43") (pin "1") (pinfunction "1_1") (pintype "passive"))
      (node (ref "C44") (pin "1") (pinfunction "1_1") (pintype "passive"))
      (node (ref "C45") (pin "1") (pinfunction "1_1") (pintype "passive"))
      (node (ref "C46") (pin "1") (pinfunction "1_1") (pintype "passive"))
      (node (ref "C47") (pin "1") (pinfunction "1_1") (pintype "passive"))
      (node (ref "C48") (pin "1") (pinfunction "1_1") (pintype "passive"))
      (node (ref "R14") (pin "1") (pinfunction "1_1") (pintype "passive"))
      (node (ref "R15") (pin "1") (pinfunction "1_1") (pintype "passive"))
      (node (ref "R19") (pin "1") (pinfunction "1_1") (pintype "passive"))
      (node (ref "R20") (pin "1") (pinfunction "1_1") (pintype "passive"))
      (node (ref "R22") (pin "1") (pinfunction "1_1") (pintype "passive"))
      (node (ref "R25") (pin "1") (pinfunction "1_1") (pintype "passive"))
      (node (ref "R26") (pin "1") (pinfunction "1_1") (pintype "passive"))
      (node (ref "U10") (pin "11") (pinfunction "EP_11") (pintype "passive"))
      (node (ref "U10") (pin "4") (pinfunction "PGND_4") (pintype "passive"))
      (node (ref "U10") (pin "8") (pinfunction "GND_8") (pintype "passive"))
      (node (ref "U11") (pin "11") (pinfunction "PAD_11") (pintype "passive"))
      (node (ref "U11") (pin "6") (pinfunction "GND_6") (pintype "passive"))
      (node (ref "U12") (pin "11") (pinfunction "PAD_11") (pintype "passive"))
      (node (ref "U12") (pin "6") (pinfunction "GND_6") (pintype "passive"))
      (node (ref "U5") (pin "10") (pinfunction "0P4V_10") (pintype "passive"))
      (node (ref "U5") (pin "6") (pinfunction "3P2V_6") (pintype "passive"))
      (node (ref "U5") (pin "7") (pinfunction "GND_7") (pintype "passive"))
      (node (ref "U5") (pin "E1") (pinfunction "PAD_E1") (pintype "passive"))
      (node (ref "U6") (pin "21") (pinfunction "EP_21") (pintype "passive"))
      (node (ref "U6") (pin "7") (pinfunction "GND_7") (pintype "passive"))
      (node (ref "U7") (pin "11") (pinfunction "PAD_11") (pintype "passive"))
      (node (ref "U7") (pin "6") (pinfunction "GND_6") (pintype "passive"))
      (node (ref "U8") (pin "11") (pinfunction "PAD_11") (pintype "passive"))
      (node (ref "U8") (pin "6") (pinfunction "GND_6") (pintype "passive"))
      (node (ref "U9") (pin "11") (pinfunction "PAD_11") (pintype "passive"))
      (node (ref "U9") (pin "6") (pinfunction "GND_6") (pintype "passive"))
    )
    (net (code "15") (name "Net-(U5-NR)") (class "Default")
      (node (ref "C21") (pin "2") (pinfunction "2_2") (pintype "passive"))
      (node (ref "U5") (pin "14") (pinfunction "NR_14") (pintype "passive"))
    )
    (net (code "16") (name "Net-(U6-FB)") (class "Default")
      (node (ref "C23") (pin "1") (pinfunction "1_1") (pintype "passive"))
      (node (ref "R12") (pin "1") (pinfunction "1_1") (pintype "passive"))
      (node (ref "R14") (pin "2") (pinfunction "2_2") (pintype "passive"))
      (node (ref "U6") (pin "3") (pinfunction "FB_3") (pintype "passive"))
    )
    (net (code "17") (name "Net-(U6-NR{slash}SS)") (class "Default")
      (node (ref "C27") (pin "2") (pinfunction "2_2") (pintype "passive"))
      (node (ref "U6") (pin "14") (pinfunction "NR/SS_14") (pintype "passive"))
    )
    (net (code "18") (name "Net-(U7-FB)") (class "Default")
      (node (ref "R13") (pin "1") (pinfunction "1_1") (pintype "passive"))
      (node (ref "R15") (pin "2") (pinfunction "2_2") (pintype "passive"))
      (node (ref "U7") (pin "8") (pinfunction "FB_8") (pintype "passive"))
    )
    (net (code "19") (name "Net-(U7-SS)") (class "Default")
      (node (ref "C28") (pin "2") (pinfunction "2_2") (pintype "passive"))
      (node (ref "U7") (pin "7") (pinfunction "SS_7") (pintype "passive"))
    )
    (net (code "20") (name "Net-(U8-FB)") (class "Default")
      (node (ref "R17") (pin "1") (pinfunction "1_1") (pintype "passive"))
      (node (ref "R19") (pin "2") (pinfunction "2_2") (pintype "passive"))
      (node (ref "U8") (pin "8") (pinfunction "FB_8") (pintype "passive"))
    )
    (net (code "21") (name "Net-(U8-SS)") (class "Default")
      (node (ref "C36") (pin "2") (pinfunction "2_2") (pintype "passive"))
      (node (ref "U8") (pin "7") (pinfunction "SS_7") (pintype "passive"))
    )
    (net (code "22") (name "Net-(U9-FB)") (class "Default")
      (node (ref "R18") (pin "1") (pinfunction "1_1") (pintype "passive"))
      (node (ref "R20") (pin "2") (pinfunction "2_2") (pintype "passive"))
      (node (ref "U9") (pin "8") (pinfunction "FB_8") (pintype "passive"))
    )
    (net (code "23") (name "Net-(U9-SS)") (class "Default")
      (node (ref "C37") (pin "2") (pinfunction "2_2") (pintype "passive"))
      (node (ref "U9") (pin "7") (pinfunction "SS_7") (pintype "passive"))
    )
    (net (code "24") (name "Net-(U10-REFIN)") (class "Default")
      (node (ref "C38") (pin "2") (pinfunction "2_2") (pintype "passive"))
      (node (ref "R21") (pin "1") (pinfunction "1_1") (pintype "passive"))
      (node (ref "R22") (pin "2") (pinfunction "2_2") (pintype "passive"))
      (node (ref "U10") (pin "1") (pinfunction "REFIN_1") (pintype "passive"))
    )
    (net (code "25") (name "Net-(U11-FB)") (class "Default")
      (node (ref "R23") (pin "1") (pinfunction "1_1") (pintype "passive"))
      (node (ref "R25") (pin "2") (pinfunction "2_2") (pintype "passive"))
      (node (ref "U11") (pin "8") (pinfunction "FB_8") (pintype "passive"))
    )
    (net (code "26") (name "Net-(U11-SS)") (class "Default")
      (node (ref "C47") (pin "2") (pinfunction "2_2") (pintype "passive"))
      (node (ref "U11") (pin "7") (pinfunction "SS_7") (pintype "passive"))
    )
    (net (code "27") (name "Net-(U12-FB)") (class "Default")
      (node (ref "R24") (pin "1") (pinfunction "1_1") (pintype "passive"))
      (node (ref "R26") (pin "2") (pinfunction "2_2") (pintype "passive"))
      (node (ref "U12") (pin "8") (pinfunction "FB_8") (pintype "passive"))
    )
    (net (code "28") (name "Net-(U12-SS)") (class "Default")
      (node (ref "C48") (pin "2") (pinfunction "2_2") (pintype "passive"))
      (node (ref "U12") (pin "7") (pinfunction "SS_7") (pintype "passive"))
    )
    (net (code "29") (name "unconnected-(U5-0P1V-Pad12)") (class "Default")
      (node (ref "U5") (pin "12") (pinfunction "0P1V_12") (pintype "passive+no_connect"))
    )
    (net (code "30") (name "unconnected-(U5-0P2V-Pad11)") (class "Default")
      (node (ref "U5") (pin "11") (pinfunction "0P2V_11") (pintype "passive+no_connect"))
    )
    (net (code "31") (name "unconnected-(U5-0P8V-Pad9)") (class "Default")
      (node (ref "U5") (pin "9") (pinfunction "0P8V_9") (pintype "passive+no_connect"))
    )
    (net (code "32") (name "unconnected-(U5-1P6V-Pad8)") (class "Default")
      (node (ref "U5") (pin "8") (pinfunction "1P6V_8") (pintype "passive+no_connect"))
    )
    (net (code "33") (name "unconnected-(U5-6P4V1-Pad5)") (class "Default")
      (node (ref "U5") (pin "5") (pinfunction "6P4V1_5") (pintype "passive+no_connect"))
    )
    (net (code "34") (name "unconnected-(U5-6P4V2-Pad4)") (class "Default")
      (node (ref "U5") (pin "4") (pinfunction "6P4V2_4") (pintype "passive+no_connect"))
    )
    (net (code "35") (name "unconnected-(U5-NC-Pad2)") (class "Default")
      (node (ref "U5") (pin "2") (pinfunction "NC_2") (pintype "passive+no_connect"))
    )
    (net (code "36") (name "unconnected-(U5-NC-Pad17)") (class "Default")
      (node (ref "U5") (pin "17") (pinfunction "NC_17") (pintype "passive+no_connect"))
    )
    (net (code "37") (name "unconnected-(U5-NC-Pad18)") (class "Default")
      (node (ref "U5") (pin "18") (pinfunction "NC_18") (pintype "passive+no_connect"))
    )
    (net (code "38") (name "unconnected-(U5-NC-Pad19)") (class "Default")
      (node (ref "U5") (pin "19") (pinfunction "NC_19") (pintype "passive+no_connect"))
    )
    (net (code "39") (name "unconnected-(U6-NC-Pad2)") (class "Default")
      (node (ref "U6") (pin "2") (pinfunction "NC_2") (pintype "passive+no_connect"))
    )
    (net (code "40") (name "unconnected-(U6-NC-Pad4)") (class "Default")
      (node (ref "U6") (pin "4") (pinfunction "NC_4") (pintype "passive+no_connect"))
    )
    (net (code "41") (name "unconnected-(U6-NC-Pad5)") (class "Default")
      (node (ref "U6") (pin "5") (pinfunction "NC_5") (pintype "passive+no_connect"))
    )
    (net (code "42") (name "unconnected-(U6-NC-Pad6)") (class "Default")
      (node (ref "U6") (pin "6") (pinfunction "NC_6") (pintype "passive+no_connect"))
    )
    (net (code "43") (name "unconnected-(U6-NC-Pad8)") (class "Default")
      (node (ref "U6") (pin "8") (pinfunction "NC_8") (pintype "passive+no_connect"))
    )
    (net (code "44") (name "unconnected-(U6-NC-Pad9)") (class "Default")
      (node (ref "U6") (pin "9") (pinfunction "NC_9") (pintype "passive+no_connect"))
    )
    (net (code "45") (name "unconnected-(U6-NC-Pad10)") (class "Default")
      (node (ref "U6") (pin "10") (pinfunction "NC_10") (pintype "passive+no_connect"))
    )
    (net (code "46") (name "unconnected-(U6-NC-Pad11)") (class "Default")
      (node (ref "U6") (pin "11") (pinfunction "NC_11") (pintype "passive+no_connect"))
    )
    (net (code "47") (name "unconnected-(U6-NC-Pad12)") (class "Default")
      (node (ref "U6") (pin "12") (pinfunction "NC_12") (pintype "passive+no_connect"))
    )
    (net (code "48") (name "unconnected-(U6-NC-Pad17)") (class "Default")
      (node (ref "U6") (pin "17") (pinfunction "NC_17") (pintype "passive+no_connect"))
    )
    (net (code "49") (name "unconnected-(U6-NC-Pad18)") (class "Default")
      (node (ref "U6") (pin "18") (pinfunction "NC_18") (pintype "passive+no_connect"))
    )
    (net (code "50") (name "unconnected-(U6-NC-Pad19)") (class "Default")
      (node (ref "U6") (pin "19") (pinfunction "NC_19") (pintype "passive+no_connect"))
    )
    (net (code "51") (name "unconnected-(U7-PG-Pad3)") (class "Default")
      (node (ref "U7") (pin "3") (pinfunction "PG_3") (pintype "passive+no_connect"))
    )
    (net (code "52") (name "unconnected-(U9-PG-Pad3)") (class "Default")
      (node (ref "U9") (pin "3") (pinfunction "PG_3") (pintype "passive+no_connect"))
    )
    (net (code "53") (name "unconnected-(U10-PGOOD-Pad9)") (class "Default")
      (node (ref "U10") (pin "9") (pinfunction "PGOOD_9") (pintype "passive+no_connect"))
    )
    (net (code "54") (name "unconnected-(U11-PG-Pad3)") (class "Default")
      (node (ref "U11") (pin "3") (pinfunction "PG_3") (pintype "passive+no_connect"))
    )
    (net (code "55") (name "unconnected-(U12-PG-Pad3)") (class "Default")
      (node (ref "U12") (pin "3") (pinfunction "PG_3") (pintype "passive+no_connect"))
    )
  )
)
